# CAN.net
KiCad netlist of a schematic drawn in Altium Designer
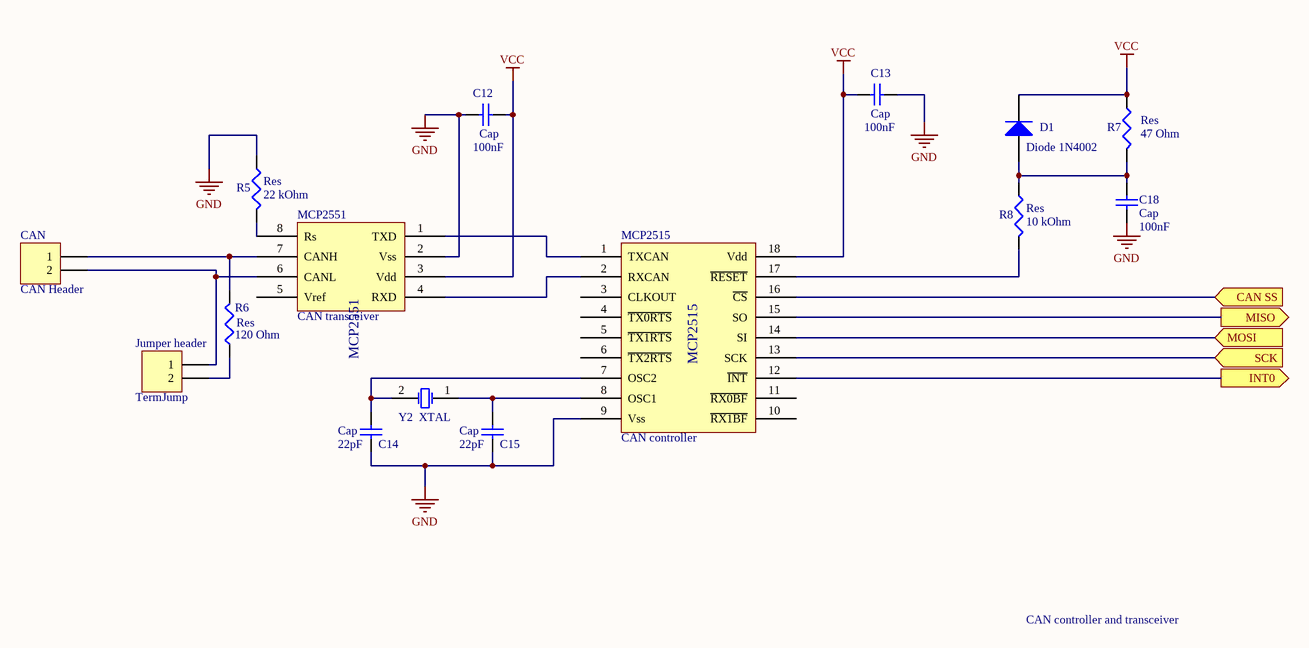
[diagram p0: CAN.SchDoc]

(export (version "E")
  (design (tool "Eeschema 10.0.6"))
  (components
    (comp (ref "C12")
      (value "Cap")
      (footprint "C1210")
      (description "Capacitor (Semiconductor SIM Model)")
      (fields (field (name "ALTIUM_VALUE") "100nF") (field (name "PUBLISHER") "Altium Limited"))
      (libsource (lib "Miscellaneous Devices") (part "Cap Semi"))
    )
    (comp (ref "C13")
      (value "Cap")
      (footprint "C1210")
      (description "Capacitor (Semiconductor SIM Model)")
      (fields (field (name "ALTIUM_VALUE") "100nF") (field (name "PUBLISHER") "Altium Limited"))
      (libsource (lib "Miscellaneous Devices") (part "Cap Semi"))
    )
    (comp (ref "C14")
      (value "Cap")
      (footprint "C1210")
      (description "Capacitor (Semiconductor SIM Model)")
      (fields (field (name "ALTIUM_VALUE") "22pF") (field (name "PUBLISHER") "Altium Limited"))
      (libsource (lib "Miscellaneous Devices") (part "Cap Semi"))
    )
    (comp (ref "C15")
      (value "Cap")
      (footprint "C1210")
      (description "Capacitor (Semiconductor SIM Model)")
      (fields (field (name "ALTIUM_VALUE") "22pF") (field (name "PUBLISHER") "Altium Limited"))
      (libsource (lib "Miscellaneous Devices") (part "Cap Semi"))
    )
    (comp (ref "C18")
      (value "Cap")
      (footprint "C1210")
      (description "Capacitor (Semiconductor SIM Model)")
      (fields (field (name "ALTIUM_VALUE") "100nF") (field (name "PUBLISHER") "Altium Limited"))
      (libsource (lib "Miscellaneous Devices") (part "Cap Semi"))
    )
    (comp (ref "CAN")
      (value "CAN Header")
      (footprint "HDR1X2")
      (description "Header, 2-Pin")
      (fields (field (name "PUBLISHER") "Altium Limited"))
      (libsource (lib "Miscellaneous Connectors") (part "Header 2"))
    )
    (comp (ref "D1")
      (value "Diode 1N4002")
      (footprint "DO-41")
      (description "1 Amp General Purpose Rectifier")
      (fields (field (name "PUBLISHER") "Altium Limited"))
      (libsource (lib "Miscellaneous Devices") (part "Diode 1N4002"))
    )
    (comp (ref "MCP2515")
      (value "CAN controller")
      (footprint "MCP2515 SOIC 18-PIN")
      (libsource (lib "IIDKLib") (part "MCP2515"))
    )
    (comp (ref "MCP2551")
      (value "CAN transceiver")
      (footprint "MACP2551 SOIC 8-PIN")
      (description "CAN Transceiver")
      (libsource (lib "IIDKLib") (part "MCP2551"))
    )
    (comp (ref "R5")
      (value "Res")
      (footprint "14-1210")
      (description "Resistor")
      (fields (field (name "ALTIUM_VALUE") "22 kOhm") (field (name "PUBLISHER") "Altium Limited"))
      (libsource (lib "Miscellaneous Devices") (part "Res3"))
    )
    (comp (ref "R6")
      (value "Res")
      (footprint "14-1210")
      (description "Resistor")
      (fields (field (name "ALTIUM_VALUE") "120 Ohm") (field (name "PUBLISHER") "Altium Limited"))
      (libsource (lib "Miscellaneous Devices") (part "Res3"))
    )
    (comp (ref "R7")
      (value "Res")
      (footprint "14-1210")
      (description "Resistor")
      (fields (field (name "ALTIUM_VALUE") "47 Ohm") (field (name "PUBLISHER") "Altium Limited"))
      (libsource (lib "Miscellaneous Devices") (part "Res3"))
    )
    (comp (ref "R8")
      (value "Res")
      (footprint "14-1210")
      (description "Resistor")
      (fields (field (name "ALTIUM_VALUE") "10 kOhm") (field (name "PUBLISHER") "Altium Limited"))
      (libsource (lib "Miscellaneous Devices") (part "Res3"))
    )
    (comp (ref "TermJump")
      (value "Jumper header")
      (footprint "HDR1X2")
      (description "Header, 2-Pin")
      (fields (field (name "PUBLISHER") "Altium Limited"))
      (libsource (lib "Miscellaneous Connectors") (part "Header 2"))
    )
    (comp (ref "Y2")
      (value "XTAL")
      (footprint "R38")
      (description "Crystal Oscillator")
      (fields (field (name "PUBLISHER") "Altium Limited"))
      (libsource (lib "Miscellaneous Devices") (part "XTAL"))
    )
  )
  (nets
    (net (code "1") (name "/CAN SS") (class "Default")
      (node (ref "MCP2515") (pin "16") (pinfunction "~{CS}_16") (pintype "passive"))
    )
    (net (code "2") (name "/INT0") (class "Default")
      (node (ref "MCP2515") (pin "12") (pinfunction "~{INT}_12") (pintype "passive"))
    )
    (net (code "3") (name "/MISO") (class "Default")
      (node (ref "MCP2515") (pin "15") (pinfunction "SO_15") (pintype "passive"))
    )
    (net (code "4") (name "/MOSI") (class "Default")
      (node (ref "MCP2515") (pin "14") (pinfunction "SI_14") (pintype "passive"))
    )
    (net (code "5") (name "/SCK") (class "Default")
      (node (ref "MCP2515") (pin "13") (pinfunction "SCK_13") (pintype "passive"))
    )
    (net (code "6") (name "GND") (class "Default")
      (node (ref "C12") (pin "2") (pinfunction "2_2") (pintype "passive"))
      (node (ref "C13") (pin "1") (pinfunction "1_1") (pintype "passive"))
      (node (ref "C14") (pin "2") (pinfunction "2_2") (pintype "passive"))
      (node (ref "C15") (pin "2") (pinfunction "2_2") (pintype "passive"))
      (node (ref "C18") (pin "2") (pinfunction "2_2") (pintype "passive"))
      (node (ref "MCP2515") (pin "9") (pinfunction "Vss_9") (pintype "passive"))
      (node (ref "MCP2551") (pin "2") (pinfunction "Vss_2") (pintype "power_in"))
      (node (ref "R5") (pin "1") (pinfunction "1_1") (pintype "passive"))
    )
    (net (code "7") (name "Net-(D1-A)") (class "Default")
      (node (ref "C18") (pin "1") (pinfunction "1_1") (pintype "passive"))
      (node (ref "D1") (pin "1") (pinfunction "A_1") (pintype "passive"))
      (node (ref "R7") (pin "2") (pinfunction "2_2") (pintype "passive"))
      (node (ref "R8") (pin "1") (pinfunction "1_1") (pintype "passive"))
    )
    (net (code "8") (name "Net-(MCP2515-OSC1)") (class "Default")
      (node (ref "C15") (pin "1") (pinfunction "1_1") (pintype "passive"))
      (node (ref "MCP2515") (pin "8") (pinfunction "OSC1_8") (pintype "passive"))
      (node (ref "Y2") (pin "1") (pinfunction "OSC1_1") (pintype "passive"))
    )
    (net (code "9") (name "Net-(MCP2515-OSC2)") (class "Default")
      (node (ref "C14") (pin "1") (pinfunction "1_1") (pintype "passive"))
      (node (ref "MCP2515") (pin "7") (pinfunction "OSC2_7") (pintype "passive"))
      (node (ref "Y2") (pin "2") (pinfunction "OSC2_2") (pintype "passive"))
    )
    (net (code "10") (name "Net-(MCP2515-RXCAN)") (class "Default")
      (node (ref "MCP2515") (pin "2") (pinfunction "RXCAN_2") (pintype "passive"))
      (node (ref "MCP2551") (pin "4") (pinfunction "RXD_4") (pintype "passive"))
    )
    (net (code "11") (name "Net-(MCP2515-TXCAN)") (class "Default")
      (node (ref "MCP2515") (pin "1") (pinfunction "TXCAN_1") (pintype "passive"))
      (node (ref "MCP2551") (pin "1") (pinfunction "TXD_1") (pintype "passive"))
    )
    (net (code "12") (name "Net-(MCP2515-~{RESET})") (class "Default")
      (node (ref "MCP2515") (pin "17") (pinfunction "~{RESET}_17") (pintype "passive"))
      (node (ref "R8") (pin "2") (pinfunction "2_2") (pintype "passive"))
    )
    (net (code "13") (name "Net-(MCP2551-CANH)") (class "Default")
      (node (ref "CAN") (pin "1") (pinfunction "1_1") (pintype "passive"))
      (node (ref "MCP2551") (pin "7") (pinfunction "CANH_7") (pintype "passive"))
      (node (ref "R6") (pin "2") (pinfunction "2_2") (pintype "passive"))
    )
    (net (code "14") (name "Net-(MCP2551-CANL)") (class "Default")
      (node (ref "CAN") (pin "2") (pinfunction "2_2") (pintype "passive"))
      (node (ref "MCP2551") (pin "6") (pinfunction "CANL_6") (pintype "passive"))
      (node (ref "TermJump") (pin "1") (pinfunction "1_1") (pintype "passive"))
    )
    (net (code "15") (name "Net-(MCP2551-Rs)") (class "Default")
      (node (ref "MCP2551") (pin "8") (pinfunction "Rs_8") (pintype "passive"))
      (node (ref "R5") (pin "2") (pinfunction "2_2") (pintype "passive"))
    )
    (net (code "16") (name "Net-(R6-Pad1)") (class "Default")
      (node (ref "R6") (pin "1") (pinfunction "1_1") (pintype "passive"))
      (node (ref "TermJump") (pin "2") (pinfunction "2_2") (pintype "passive"))
    )
    (net (code "17") (name "VCC") (class "Default")
      (node (ref "C12") (pin "1") (pinfunction "1_1") (pintype "passive"))
      (node (ref "C13") (pin "2") (pinfunction "2_2") (pintype "passive"))
      (node (ref "D1") (pin "2") (pinfunction "K_2") (pintype "passive"))
      (node (ref "MCP2515") (pin "18") (pinfunction "Vdd_18") (pintype "passive"))
      (node (ref "MCP2551") (pin "3") (pinfunction "Vdd_3") (pintype "power_in"))
      (node (ref "R7") (pin "1") (pinfunction "1_1") (pintype "passive"))
    )
    (net (code "18") (name "unconnected-(MCP2515-CLKOUT-Pad3)") (class "Default")
      (node (ref "MCP2515") (pin "3") (pinfunction "CLKOUT_3") (pintype "passive"))
    )
    (net (code "19") (name "unconnected-(MCP2515-~{RX0BF}-Pad11)") (class "Default")
      (node (ref "MCP2515") (pin "11") (pinfunction "~{RX0BF}_11") (pintype "passive"))
    )
    (net (code "20") (name "unconnected-(MCP2515-~{RX1BF}-Pad10)") (class "Default")
      (node (ref "MCP2515") (pin "10") (pinfunction "~{RX1BF}_10") (pintype "passive"))
    )
    (net (code "21") (name "unconnected-(MCP2515-~{TX0RTS}-Pad4)") (class "Default")
      (node (ref "MCP2515") (pin "4") (pinfunction "~{TX0RTS}_4") (pintype "passive"))
    )
    (net (code "22") (name "unconnected-(MCP2515-~{TX1RTS}-Pad5)") (class "Default")
      (node (ref "MCP2515") (pin "5") (pinfunction "~{TX1RTS}_5") (pintype "passive"))
    )
    (net (code "23") (name "unconnected-(MCP2515-~{TX2RTS}-Pad6)") (class "Default")
      (node (ref "MCP2515") (pin "6") (pinfunction "~{TX2RTS}_6") (pintype "passive"))
    )
    (net (code "24") (name "unconnected-(MCP2551-Vref-Pad5)") (class "Default")
      (node (ref "MCP2551") (pin "5") (pinfunction "Vref_5") (pintype "passive"))
    )
  )
)
